# Tiny84EncoderReader.net
KiCad netlist of a schematic drawn in EAGLE
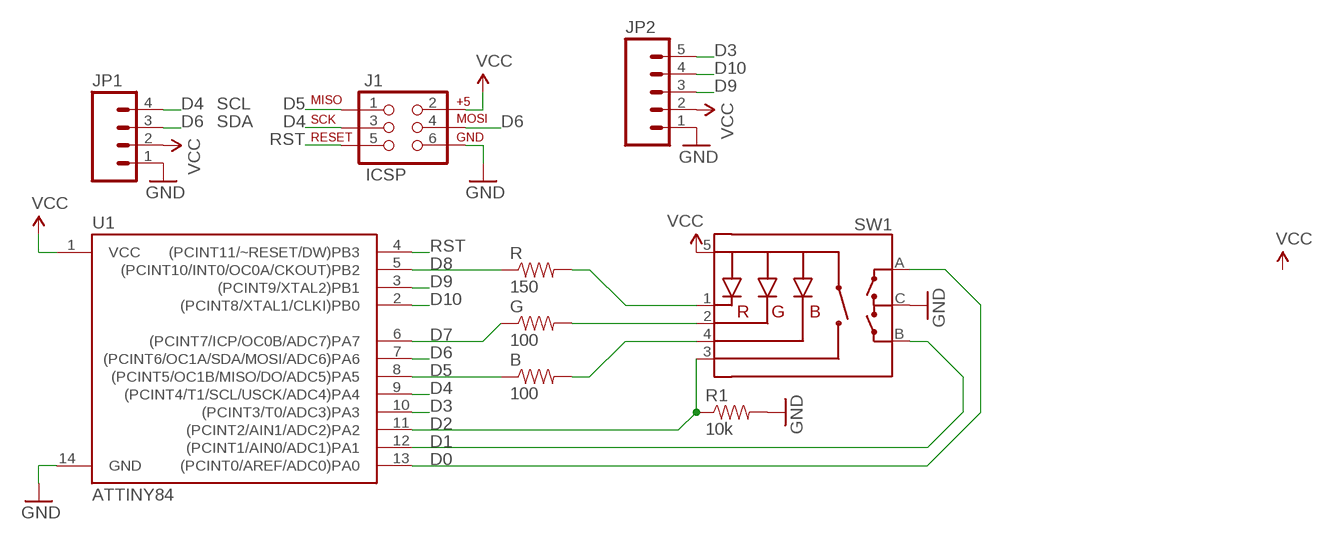
[diagram p0: schematic, sheet 1]

(export (version "E")
  (design (tool "Eeschema 10.0.6"))
  (components
    (comp (ref "B")
      (value "100")
      (footprint "eagle-import:0805")
      (libsource (lib "eagle-import") (part "RESISTOR0805-RES"))
    )
    (comp (ref "G")
      (value "100")
      (footprint "eagle-import:0805")
      (libsource (lib "eagle-import") (part "RESISTOR0805-RES"))
    )
    (comp (ref "J1")
      (value "ICSP")
      (footprint "eagle-import:2X3-NS")
      (libsource (lib "eagle-import") (part "AVR_SPI_PRG_6LABELED"))
    )
    (comp (ref "JP1")
      (value "M04PTH")
      (footprint "eagle-import:1X04")
      (libsource (lib "eagle-import") (part "M04PTH"))
    )
    (comp (ref "JP2")
      (value "M05PTH")
      (footprint "eagle-import:1X05")
      (libsource (lib "eagle-import") (part "M05PTH"))
    )
    (comp (ref "R")
      (value "150")
      (footprint "eagle-import:0805")
      (libsource (lib "eagle-import") (part "RESISTOR0805-RES"))
    )
    (comp (ref "R1")
      (value "10k")
      (footprint "eagle-import:0805")
      (libsource (lib "eagle-import") (part "RESISTOR0805-RES"))
    )
    (comp (ref "SW1")
      (value "ENCODER_RGB_CA")
      (footprint "eagle-import:ENCODER_LED_3")
      (libsource (lib "eagle-import") (part "ENCODER_RGB_CA"))
    )
    (comp (ref "U1")
      (value "ATTINY84")
      (footprint "eagle-import:SO14")
      (libsource (lib "eagle-import") (part "ATTINY84"))
    )
  )
  (nets
    (net (code "1") (name "/D0") (class "Default")
      (node (ref "SW1") (pin "A") (pinfunction "A_A") (pintype "bidirectional"))
      (node (ref "U1") (pin "13") (pinfunction "(PCINT0/AREF/ADC0)PA0_13") (pintype "bidirectional"))
    )
    (net (code "2") (name "/D1") (class "Default")
      (node (ref "SW1") (pin "B") (pinfunction "B_B") (pintype "bidirectional"))
      (node (ref "U1") (pin "12") (pinfunction "(PCINT1/AIN0/ADC1)PA1_12") (pintype "bidirectional"))
    )
    (net (code "3") (name "/D2") (class "Default")
      (node (ref "R1") (pin "1") (pinfunction "1_1") (pintype "passive"))
      (node (ref "SW1") (pin "3") (pinfunction "SW_3") (pintype "passive"))
      (node (ref "U1") (pin "11") (pinfunction "(PCINT2/AIN1/ADC2)PA2_11") (pintype "bidirectional"))
    )
    (net (code "4") (name "/D3") (class "Default")
      (node (ref "JP2") (pin "5") (pinfunction "5_5") (pintype "passive"))
      (node (ref "U1") (pin "10") (pinfunction "(PCINT3/T0/ADC3)PA3_10") (pintype "bidirectional"))
    )
    (net (code "5") (name "/D4") (class "Default")
      (node (ref "J1") (pin "3") (pinfunction "SCK_3") (pintype "passive"))
      (node (ref "JP1") (pin "4") (pinfunction "4_4") (pintype "passive"))
      (node (ref "U1") (pin "9") (pinfunction "(PCINT4/T1/SCL/USCK/ADC4)PA4_9") (pintype "bidirectional"))
    )
    (net (code "6") (name "/D5") (class "Default")
      (node (ref "B") (pin "1") (pinfunction "1_1") (pintype "passive"))
      (node (ref "J1") (pin "1") (pinfunction "MISO_1") (pintype "passive"))
      (node (ref "U1") (pin "8") (pinfunction "(PCINT5/OC1B/MISO/DO/ADC5)PA5_8") (pintype "bidirectional"))
    )
    (net (code "7") (name "/D6") (class "Default")
      (node (ref "J1") (pin "4") (pinfunction "MOSI_4") (pintype "passive"))
      (node (ref "JP1") (pin "3") (pinfunction "3_3") (pintype "passive"))
      (node (ref "U1") (pin "7") (pinfunction "(PCINT6/OC1A/SDA/MOSI/ADC6)PA6_7") (pintype "bidirectional"))
    )
    (net (code "8") (name "/D7") (class "Default")
      (node (ref "G") (pin "1") (pinfunction "1_1") (pintype "passive"))
      (node (ref "U1") (pin "6") (pinfunction "(PCINT7/ICP/OC0B/ADC7)PA7_6") (pintype "bidirectional"))
    )
    (net (code "9") (name "/D8") (class "Default")
      (node (ref "R") (pin "1") (pinfunction "1_1") (pintype "passive"))
      (node (ref "U1") (pin "5") (pinfunction "(PCINT10/INT0/OC0A/CKOUT)PB2_5") (pintype "bidirectional"))
    )
    (net (code "10") (name "/D9") (class "Default")
      (node (ref "JP2") (pin "3") (pinfunction "3_3") (pintype "passive"))
      (node (ref "U1") (pin "3") (pinfunction "(PCINT9/XTAL2)PB1_3") (pintype "bidirectional"))
    )
    (net (code "11") (name "/D10") (class "Default")
      (node (ref "JP2") (pin "4") (pinfunction "4_4") (pintype "passive"))
      (node (ref "U1") (pin "2") (pinfunction "(PCINT8/XTAL1/CLKI)PB0_2") (pintype "bidirectional"))
    )
    (net (code "12") (name "/RST") (class "Default")
      (node (ref "J1") (pin "5") (pinfunction "RST_5") (pintype "passive"))
      (node (ref "U1") (pin "4") (pinfunction "(PCINT11/~{RESET/DW})PB3_4") (pintype "bidirectional"))
    )
    (net (code "13") (name "GND") (class "Default")
      (node (ref "J1") (pin "6") (pinfunction "GND_6") (pintype "passive"))
      (node (ref "JP1") (pin "1") (pinfunction "1_1") (pintype "passive"))
      (node (ref "JP2") (pin "1") (pinfunction "1_1") (pintype "passive"))
      (node (ref "R1") (pin "2") (pinfunction "2_2") (pintype "passive"))
      (node (ref "SW1") (pin "C") (pinfunction "C_C") (pintype "bidirectional"))
      (node (ref "U1") (pin "14") (pinfunction "GND_14") (pintype "bidirectional"))
    )
    (net (code "14") (name "Net-(SW1--B)") (class "Default")
      (node (ref "B") (pin "2") (pinfunction "2_2") (pintype "passive"))
      (node (ref "SW1") (pin "4") (pinfunction "-B_4") (pintype "passive"))
    )
    (net (code "15") (name "Net-(SW1--G)") (class "Default")
      (node (ref "G") (pin "2") (pinfunction "2_2") (pintype "passive"))
      (node (ref "SW1") (pin "2") (pinfunction "-G_2") (pintype "passive"))
    )
    (net (code "16") (name "Net-(SW1--R)") (class "Default")
      (node (ref "R") (pin "2") (pinfunction "2_2") (pintype "passive"))
      (node (ref "SW1") (pin "1") (pinfunction "-R_1") (pintype "passive"))
    )
    (net (code "17") (name "VCC") (class "Default")
      (node (ref "J1") (pin "2") (pinfunction "V+_2") (pintype "passive"))
      (node (ref "JP1") (pin "2") (pinfunction "2_2") (pintype "passive"))
      (node (ref "JP2") (pin "2") (pinfunction "2_2") (pintype "passive"))
      (node (ref "SW1") (pin "5") (pinfunction "+_5") (pintype "passive"))
      (node (ref "U1") (pin "1") (pinfunction "VCC_1") (pintype "bidirectional"))
    )
  )
)
